# 9_3_2_transmitter.net
KiCad netlist of a schematic drawn in EAGLE
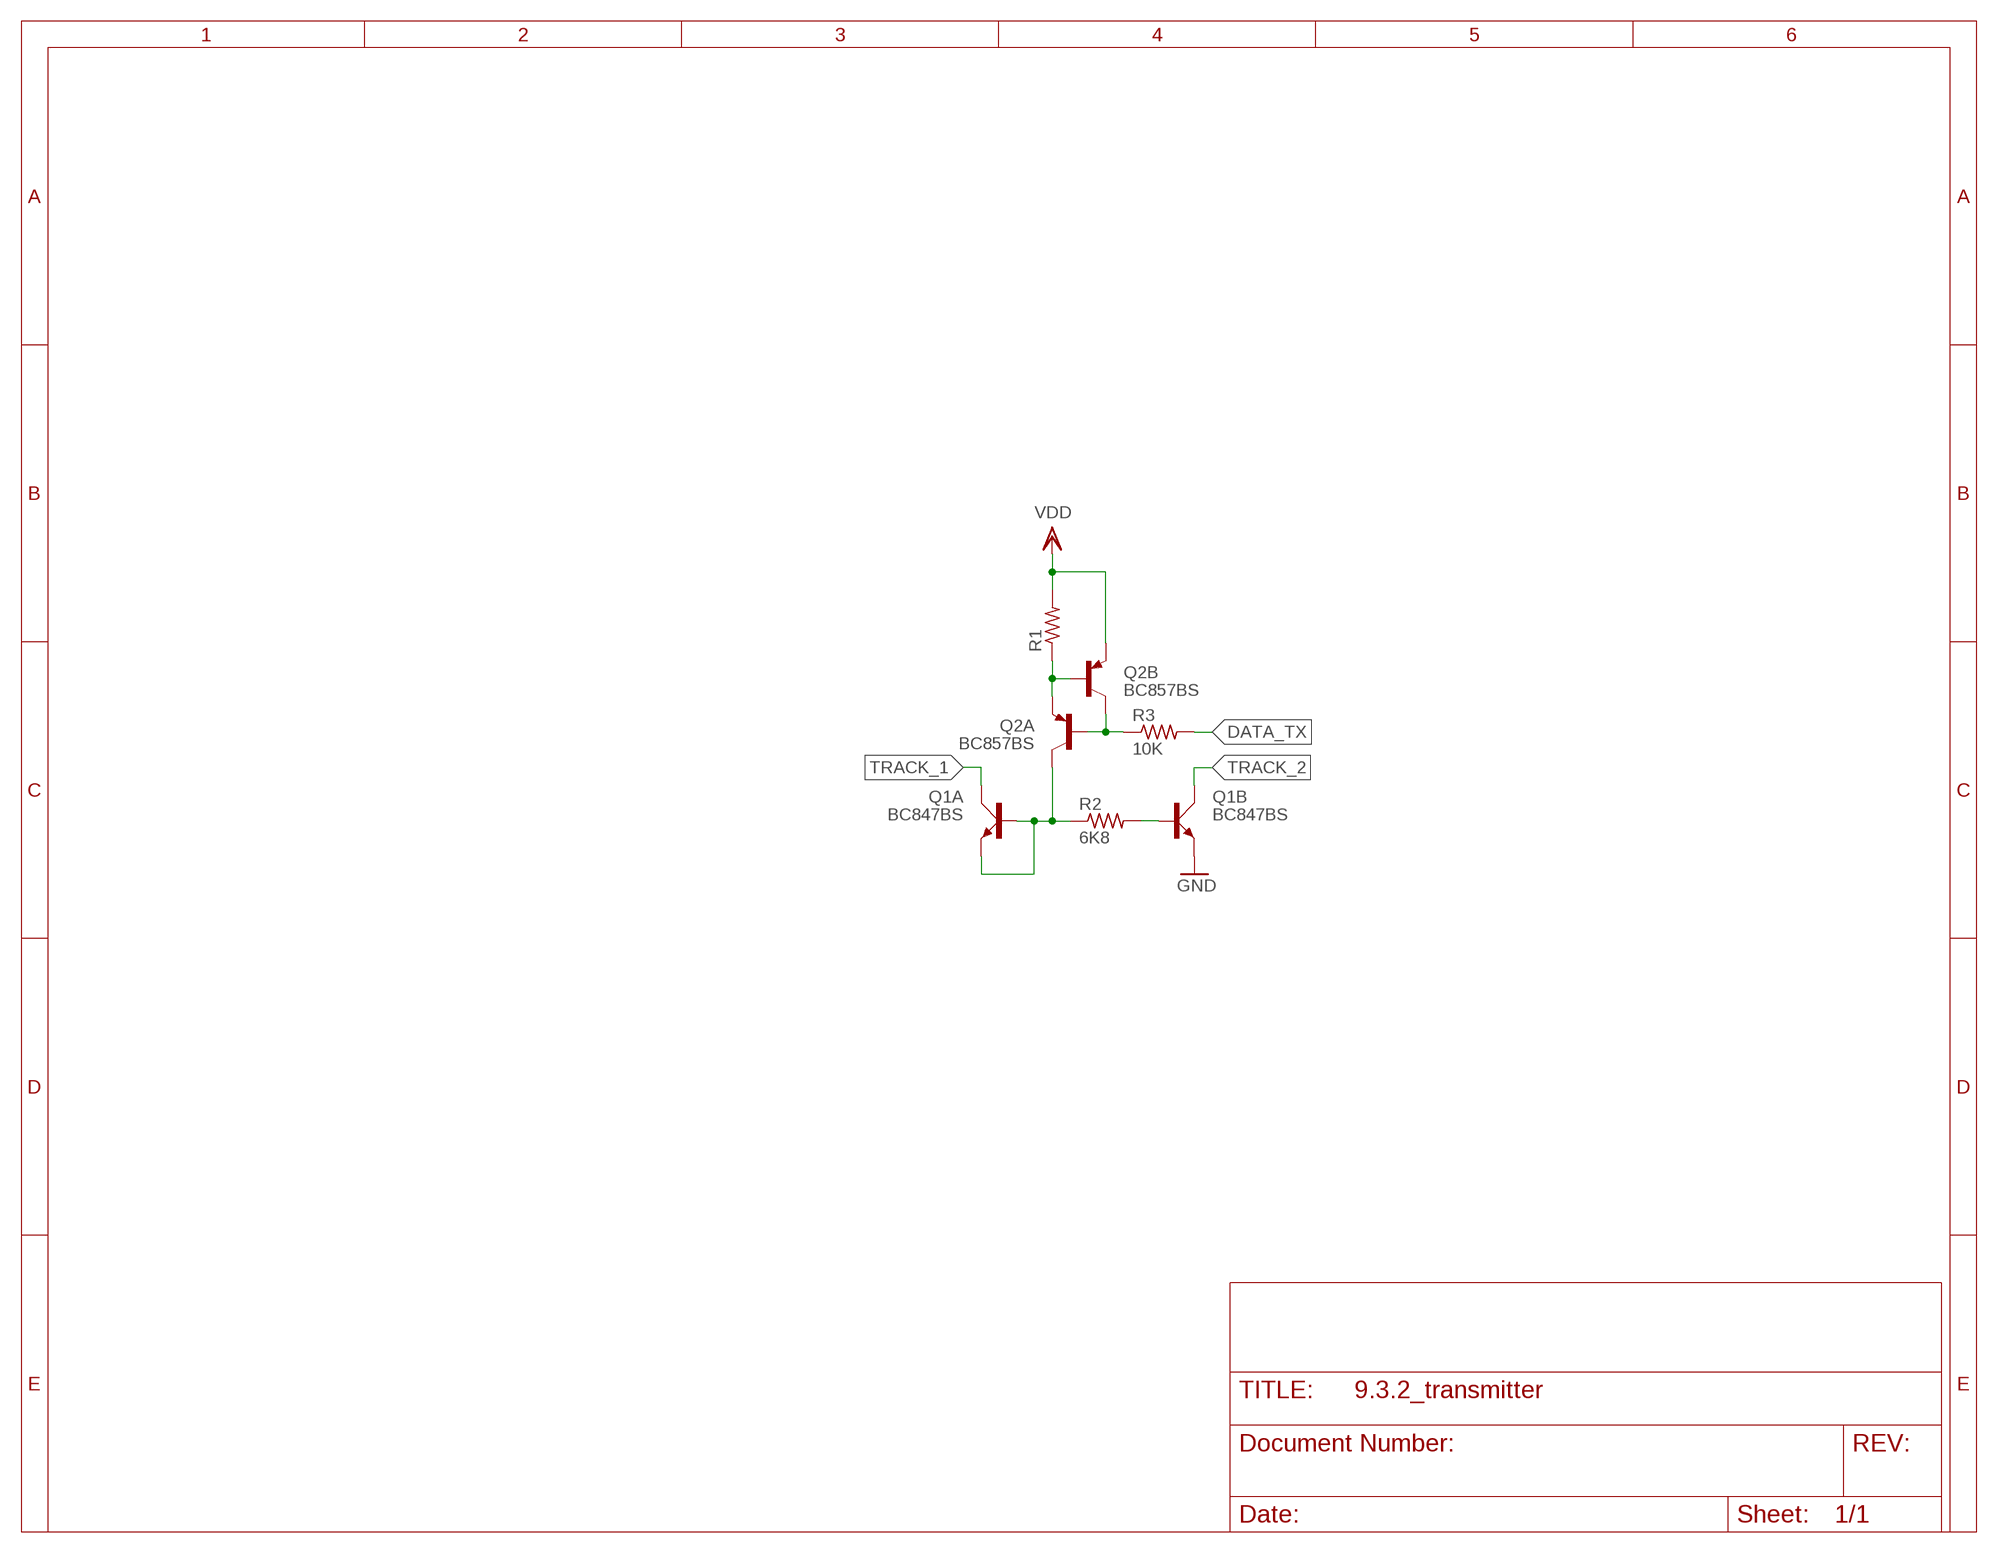
[diagram p0: schematic, sheet 1]

(export (version "E")
  (design (tool "Eeschema 10.0.6"))
  (components
    (comp (ref "Q1")
      (value "BC847BS")
      (footprint "eagle-import:SOT363_PHILIPS")
      (libsource (lib "eagle-import") (part "BC847BS"))
    )
    (comp (ref "Q2A")
      (value "BC857BS")
      (footprint "eagle-import:SOT23-BEC")
      (libsource (lib "eagle-import") (part "BC857SMDB"))
    )
    (comp (ref "Q2B")
      (value "BC857BS")
      (footprint "eagle-import:SOT23-BEC")
      (libsource (lib "eagle-import") (part "BC857SMDB"))
    )
    (comp (ref "R1")
      (value "22R")
      (footprint "eagle-import:R0402")
      (libsource (lib "eagle-import") (part "R-US_R0402"))
    )
    (comp (ref "R2")
      (value "6K8")
      (footprint "eagle-import:R0402")
      (libsource (lib "eagle-import") (part "R-US_R0402"))
    )
    (comp (ref "R3")
      (value "10K")
      (footprint "eagle-import:R0402")
      (libsource (lib "eagle-import") (part "R-US_R0402"))
    )
  )
  (nets
    (net (code "1") (name "DATA_TX") (class "Default")
      (node (ref "R3") (pin "2") (pinfunction "2_2") (pintype "passive"))
    )
    (net (code "2") (name "GND") (class "Default")
      (node (ref "Q1") (pin "4") (pinfunction "E_4") (pintype "passive"))
    )
    (net (code "3") (name "Net-(Q1A-B)") (class "Default")
      (node (ref "Q1") (pin "1") (pinfunction "E_1") (pintype "passive"))
      (node (ref "Q1") (pin "2") (pinfunction "B_2") (pintype "passive"))
      (node (ref "Q2A") (pin "C") (pinfunction "C_C") (pintype "passive"))
      (node (ref "R2") (pin "1") (pinfunction "1_1") (pintype "passive"))
    )
    (net (code "4") (name "Net-(Q1B-B)") (class "Default")
      (node (ref "Q1") (pin "5") (pinfunction "B_5") (pintype "passive"))
      (node (ref "R2") (pin "2") (pinfunction "2_2") (pintype "passive"))
    )
    (net (code "5") (name "Net-(Q2A-PadB)") (class "Default")
      (node (ref "Q2A") (pin "B") (pinfunction "B_B") (pintype "passive"))
      (node (ref "Q2B") (pin "C") (pinfunction "C_C") (pintype "passive"))
      (node (ref "R3") (pin "1") (pinfunction "1_1") (pintype "passive"))
    )
    (net (code "6") (name "Net-(Q2A-PadE)") (class "Default")
      (node (ref "Q2A") (pin "E") (pinfunction "E_E") (pintype "passive"))
      (node (ref "Q2B") (pin "B") (pinfunction "B_B") (pintype "passive"))
      (node (ref "R1") (pin "1") (pinfunction "1_1") (pintype "passive"))
    )
    (net (code "7") (name "TRACK_1") (class "Default")
      (node (ref "Q1") (pin "6") (pinfunction "C_6") (pintype "passive"))
    )
    (net (code "8") (name "TRACK_2") (class "Default")
      (node (ref "Q1") (pin "3") (pinfunction "C_3") (pintype "passive"))
    )
    (net (code "9") (name "VDD") (class "Default")
      (node (ref "Q2B") (pin "E") (pinfunction "E_E") (pintype "passive"))
      (node (ref "R1") (pin "2") (pinfunction "2_2") (pintype "passive"))
    )
  )
)
